# Arduino_MEGA2560_manual.net
KiCad netlist of a schematic drawn in EAGLE
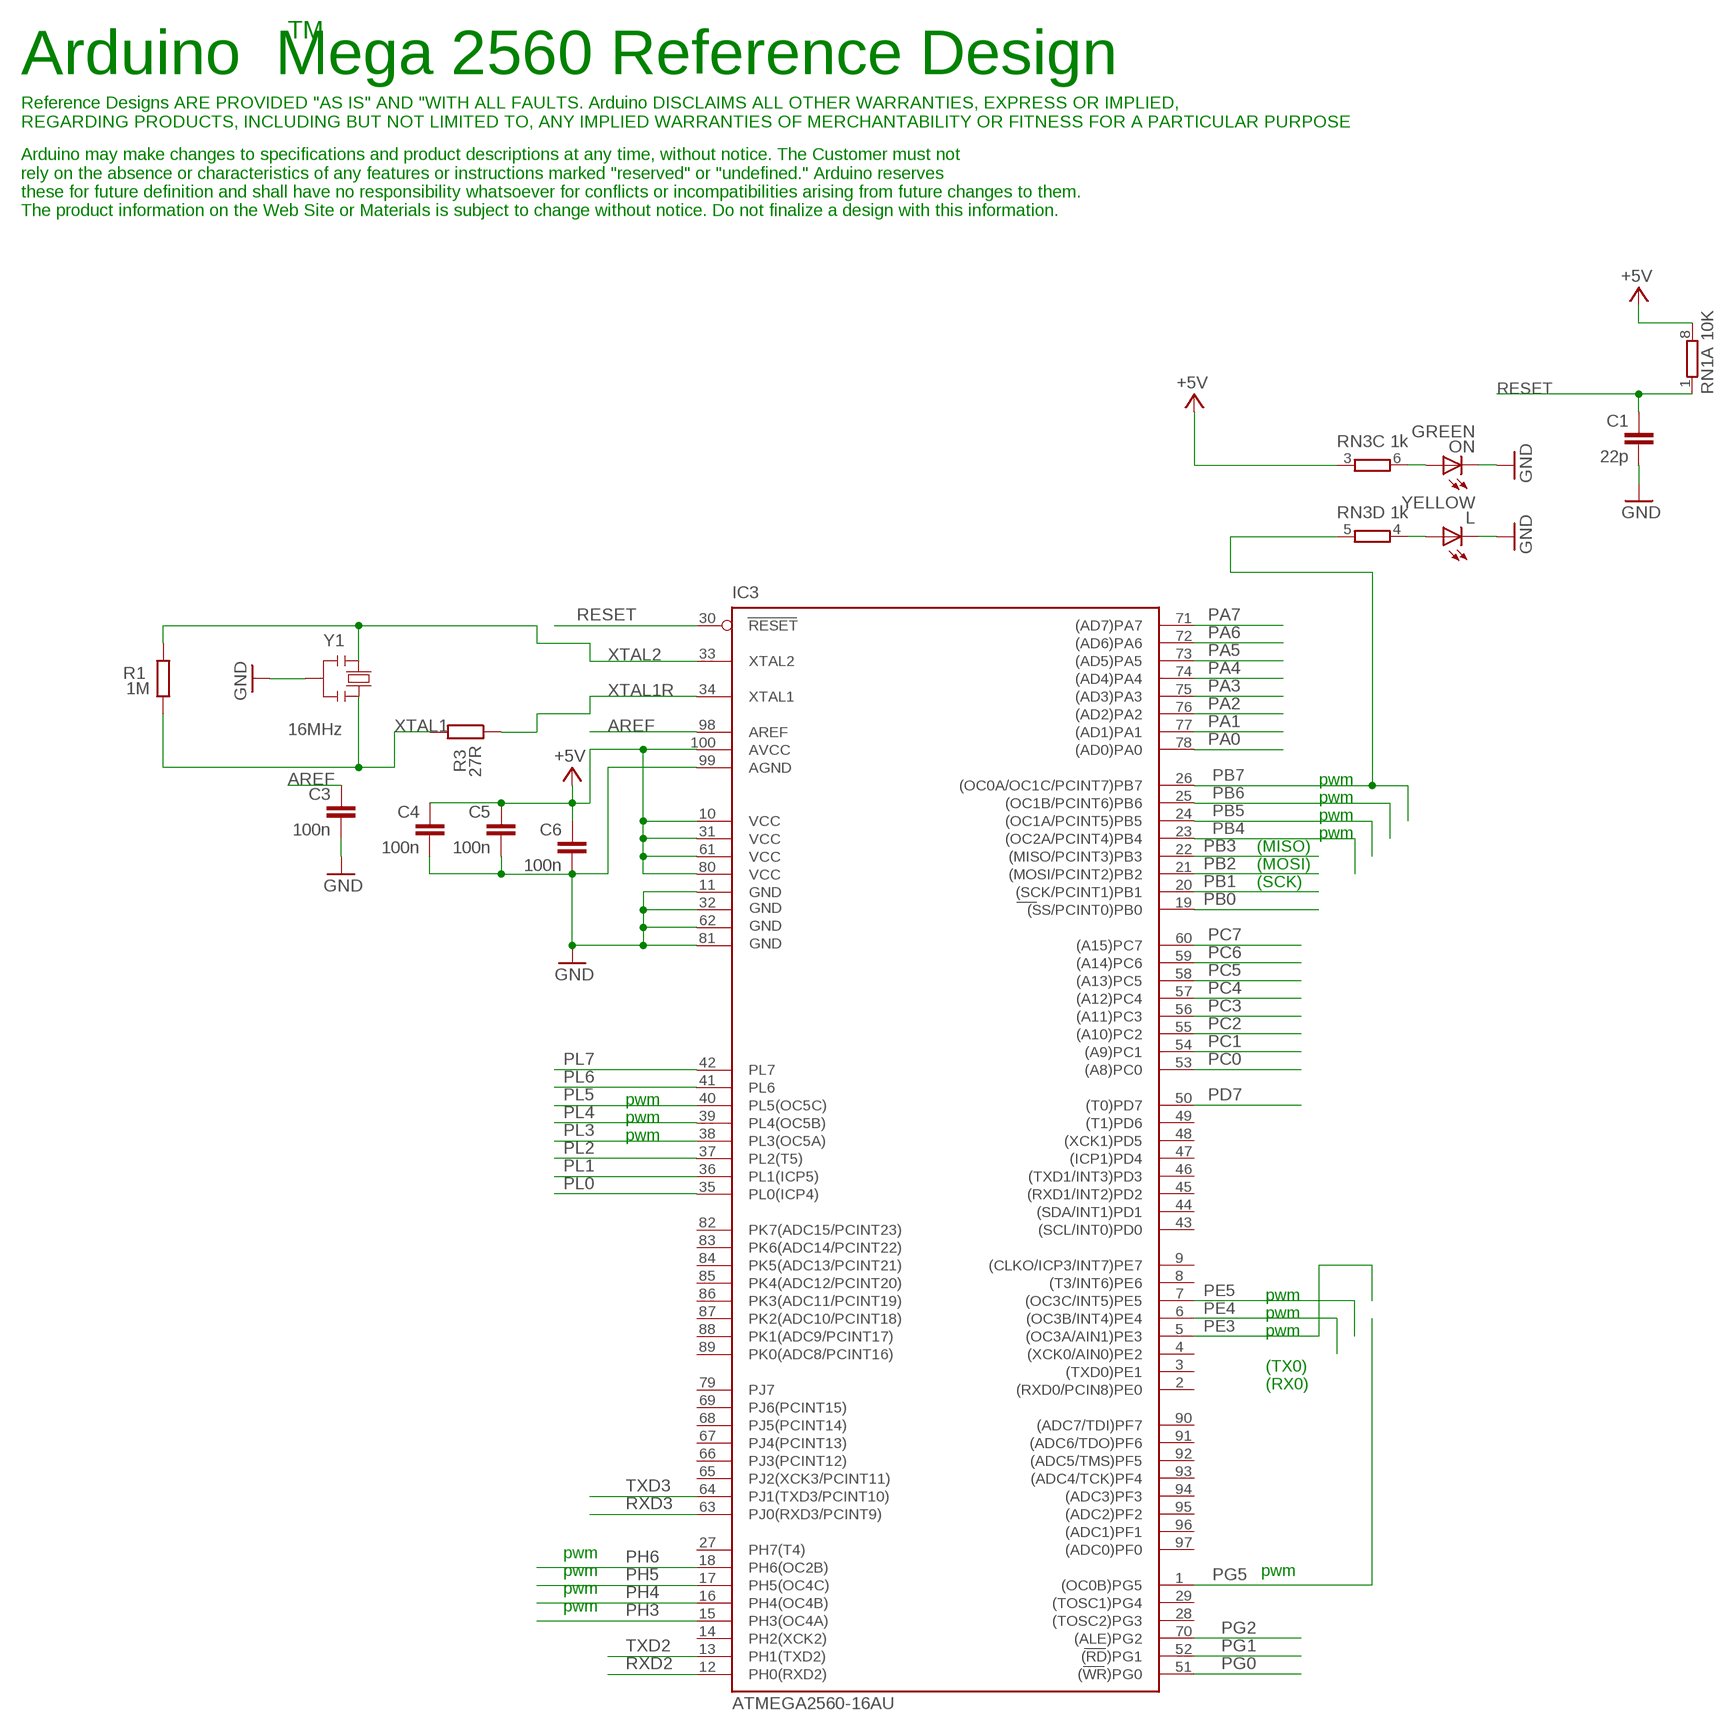
[diagram p0: schematic, sheet 1]

(export (version "E")
  (design (tool "Eeschema 10.0.6"))
  (components
    (comp (ref "C1")
      (value "22p")
      (footprint "eagle-import:C0603-ROUND")
      (libsource (lib "eagle-import") (part "C-EU0603-RND"))
    )
    (comp (ref "C3")
      (value "100n")
      (footprint "eagle-import:C0603-ROUND")
      (libsource (lib "eagle-import") (part "C-EU0603-RND"))
    )
    (comp (ref "C4")
      (value "100n")
      (footprint "eagle-import:C0603-ROUND")
      (libsource (lib "eagle-import") (part "C-EU0603-RND"))
    )
    (comp (ref "C5")
      (value "100n")
      (footprint "eagle-import:C0603-ROUND")
      (libsource (lib "eagle-import") (part "C-EU0603-RND"))
    )
    (comp (ref "C6")
      (value "100n")
      (footprint "eagle-import:C0603-ROUND")
      (libsource (lib "eagle-import") (part "C-EU0603-RND"))
    )
    (comp (ref "IC3")
      (value "ATMEGA2560-16AU")
      (footprint "eagle-import:TQFP100")
      (libsource (lib "eagle-import") (part "ATMEGAAU1280-16"))
    )
    (comp (ref "L")
      (value "YELLOW")
      (footprint "eagle-import:CHIP-LED0805")
      (libsource (lib "eagle-import") (part "LEDCHIP-LED0805"))
    )
    (comp (ref "ON")
      (value "GREEN")
      (footprint "eagle-import:CHIP-LED0805")
      (libsource (lib "eagle-import") (part "LEDCHIP-LED0805"))
    )
    (comp (ref "R1")
      (value "1M")
      (footprint "eagle-import:R0603-ROUND")
      (libsource (lib "eagle-import") (part "R-EU_R0603"))
    )
    (comp (ref "R3")
      (value "27R")
      (footprint "eagle-import:R0603-ROUND")
      (libsource (lib "eagle-import") (part "R-EU_R0603"))
    )
    (comp (ref "RN1")
      (value "10K")
      (footprint "eagle-import:CAT16")
      (libsource (lib "eagle-import") (part "4R-NCAT16"))
    )
    (comp (ref "RN3")
      (value "1k")
      (footprint "eagle-import:CAY16")
      (libsource (lib "eagle-import") (part "4R-NCAY16"))
    )
    (comp (ref "Y1")
      (value "16MHz")
      (footprint "eagle-import:RESONATOR")
      (libsource (lib "eagle-import") (part "RESONATORMU"))
    )
  )
  (nets
    (net (code "1") (name "+5V") (class "Default")
      (node (ref "C4") (pin "1") (pinfunction "1_1") (pintype "passive"))
      (node (ref "C5") (pin "1") (pinfunction "1_1") (pintype "passive"))
      (node (ref "C6") (pin "1") (pinfunction "1_1") (pintype "passive"))
      (node (ref "IC3") (pin "10") (pinfunction "VCC_10") (pintype "power_in"))
      (node (ref "IC3") (pin "100") (pinfunction "AVCC_100") (pintype "power_in"))
      (node (ref "IC3") (pin "31") (pinfunction "VCC1_31") (pintype "power_in"))
      (node (ref "IC3") (pin "61") (pinfunction "VCC2_61") (pintype "power_in"))
      (node (ref "IC3") (pin "80") (pinfunction "VCC3_80") (pintype "power_in"))
      (node (ref "RN1") (pin "8") (pinfunction "2_8") (pintype "passive"))
      (node (ref "RN3") (pin "3") (pinfunction "1_3") (pintype "passive"))
    )
    (net (code "2") (name "/AREF") (class "Default")
      (node (ref "C3") (pin "1") (pinfunction "1_1") (pintype "passive"))
      (node (ref "IC3") (pin "98") (pinfunction "AREF_98") (pintype "bidirectional"))
    )
    (net (code "3") (name "/PA0") (class "Default")
      (node (ref "IC3") (pin "78") (pinfunction "(AD0)PA0_78") (pintype "bidirectional"))
    )
    (net (code "4") (name "/PA1") (class "Default")
      (node (ref "IC3") (pin "77") (pinfunction "(AD1)PA1_77") (pintype "bidirectional"))
    )
    (net (code "5") (name "/PA2") (class "Default")
      (node (ref "IC3") (pin "76") (pinfunction "(AD2)PA2_76") (pintype "bidirectional"))
    )
    (net (code "6") (name "/PA3") (class "Default")
      (node (ref "IC3") (pin "75") (pinfunction "(AD3)PA3_75") (pintype "bidirectional"))
    )
    (net (code "7") (name "/PA4") (class "Default")
      (node (ref "IC3") (pin "74") (pinfunction "(AD4)PA4_74") (pintype "bidirectional"))
    )
    (net (code "8") (name "/PA5") (class "Default")
      (node (ref "IC3") (pin "73") (pinfunction "(AD5)PA5_73") (pintype "bidirectional"))
    )
    (net (code "9") (name "/PA6") (class "Default")
      (node (ref "IC3") (pin "72") (pinfunction "(AD6)PA6_72") (pintype "bidirectional"))
    )
    (net (code "10") (name "/PA7") (class "Default")
      (node (ref "IC3") (pin "71") (pinfunction "(AD7)PA7_71") (pintype "bidirectional"))
    )
    (net (code "11") (name "/PB0") (class "Default")
      (node (ref "IC3") (pin "19") (pinfunction "(SS/PCINT0)PB0_19") (pintype "bidirectional"))
    )
    (net (code "12") (name "/PB1") (class "Default")
      (node (ref "IC3") (pin "20") (pinfunction "(SCK/PCINT1)PB1_20") (pintype "bidirectional"))
    )
    (net (code "13") (name "/PB2") (class "Default")
      (node (ref "IC3") (pin "21") (pinfunction "(MOSI/PCINT2)PB2_21") (pintype "bidirectional"))
    )
    (net (code "14") (name "/PB3") (class "Default")
      (node (ref "IC3") (pin "22") (pinfunction "(MISO/PCINT3)PB3_22") (pintype "bidirectional"))
    )
    (net (code "15") (name "/PB4") (class "Default")
      (node (ref "IC3") (pin "23") (pinfunction "(OC2A/PCINT4)PB4_23") (pintype "bidirectional"))
    )
    (net (code "16") (name "/PB5") (class "Default")
      (node (ref "IC3") (pin "24") (pinfunction "(OC1A/PCINT5)PB5_24") (pintype "bidirectional"))
    )
    (net (code "17") (name "/PB6") (class "Default")
      (node (ref "IC3") (pin "25") (pinfunction "(OC1B/PCINT6)PB6_25") (pintype "bidirectional"))
    )
    (net (code "18") (name "/PB7") (class "Default")
      (node (ref "IC3") (pin "26") (pinfunction "(OC0A/OC1C/PCINT7)PB7_26") (pintype "bidirectional"))
      (node (ref "RN3") (pin "5") (pinfunction "2_5") (pintype "passive"))
    )
    (net (code "19") (name "/PC0") (class "Default")
      (node (ref "IC3") (pin "53") (pinfunction "(A8)PC0_53") (pintype "bidirectional"))
    )
    (net (code "20") (name "/PC1") (class "Default")
      (node (ref "IC3") (pin "54") (pinfunction "(A9)PC1_54") (pintype "bidirectional"))
    )
    (net (code "21") (name "/PC2") (class "Default")
      (node (ref "IC3") (pin "55") (pinfunction "(A10)PC2_55") (pintype "bidirectional"))
    )
    (net (code "22") (name "/PC3") (class "Default")
      (node (ref "IC3") (pin "56") (pinfunction "(A11)PC3_56") (pintype "bidirectional"))
    )
    (net (code "23") (name "/PC4") (class "Default")
      (node (ref "IC3") (pin "57") (pinfunction "(A12)PC4_57") (pintype "bidirectional"))
    )
    (net (code "24") (name "/PC5") (class "Default")
      (node (ref "IC3") (pin "58") (pinfunction "(A13)PC5_58") (pintype "bidirectional"))
    )
    (net (code "25") (name "/PC6") (class "Default")
      (node (ref "IC3") (pin "59") (pinfunction "(A14)PC6_59") (pintype "bidirectional"))
    )
    (net (code "26") (name "/PC7") (class "Default")
      (node (ref "IC3") (pin "60") (pinfunction "(A15)PC7_60") (pintype "bidirectional"))
    )
    (net (code "27") (name "/PD7") (class "Default")
      (node (ref "IC3") (pin "50") (pinfunction "(T0)PD7_50") (pintype "bidirectional"))
    )
    (net (code "28") (name "/PE3") (class "Default")
      (node (ref "IC3") (pin "5") (pinfunction "(OC3A/AIN1)PE3_5") (pintype "bidirectional"))
    )
    (net (code "29") (name "/PE4") (class "Default")
      (node (ref "IC3") (pin "6") (pinfunction "(OC3B/INT4)PE4_6") (pintype "bidirectional"))
    )
    (net (code "30") (name "/PE5") (class "Default")
      (node (ref "IC3") (pin "7") (pinfunction "(OC3C/INT5)PE5_7") (pintype "bidirectional"))
    )
    (net (code "31") (name "/PG0") (class "Default")
      (node (ref "IC3") (pin "51") (pinfunction "(WR)PG0_51") (pintype "bidirectional"))
    )
    (net (code "32") (name "/PG1") (class "Default")
      (node (ref "IC3") (pin "52") (pinfunction "(RD)PG1_52") (pintype "bidirectional"))
    )
    (net (code "33") (name "/PG2") (class "Default")
      (node (ref "IC3") (pin "70") (pinfunction "(ALE)PG2_70") (pintype "bidirectional"))
    )
    (net (code "34") (name "/PG5") (class "Default")
      (node (ref "IC3") (pin "1") (pinfunction "(OC0B)PG5_1") (pintype "bidirectional"))
    )
    (net (code "35") (name "/PH3") (class "Default")
      (node (ref "IC3") (pin "15") (pinfunction "PH3(OC4A)_15") (pintype "bidirectional"))
    )
    (net (code "36") (name "/PH4") (class "Default")
      (node (ref "IC3") (pin "16") (pinfunction "PH4(OC4B)_16") (pintype "bidirectional"))
    )
    (net (code "37") (name "/PH5") (class "Default")
      (node (ref "IC3") (pin "17") (pinfunction "PH5(OC4C)_17") (pintype "bidirectional"))
    )
    (net (code "38") (name "/PH6") (class "Default")
      (node (ref "IC3") (pin "18") (pinfunction "PH6(OC2B)_18") (pintype "bidirectional"))
    )
    (net (code "39") (name "/PL0") (class "Default")
      (node (ref "IC3") (pin "35") (pinfunction "PL0(ICP4)_35") (pintype "bidirectional"))
    )
    (net (code "40") (name "/PL1") (class "Default")
      (node (ref "IC3") (pin "36") (pinfunction "PL1(ICP5)_36") (pintype "bidirectional"))
    )
    (net (code "41") (name "/PL2") (class "Default")
      (node (ref "IC3") (pin "37") (pinfunction "PL2(T5)_37") (pintype "bidirectional"))
    )
    (net (code "42") (name "/PL3") (class "Default")
      (node (ref "IC3") (pin "38") (pinfunction "PL3(OC5A)_38") (pintype "bidirectional"))
    )
    (net (code "43") (name "/PL4") (class "Default")
      (node (ref "IC3") (pin "39") (pinfunction "PL4(OC5B)_39") (pintype "bidirectional"))
    )
    (net (code "44") (name "/PL5") (class "Default")
      (node (ref "IC3") (pin "40") (pinfunction "PL5(OC5C)_40") (pintype "bidirectional"))
    )
    (net (code "45") (name "/PL6") (class "Default")
      (node (ref "IC3") (pin "41") (pinfunction "PL6_41") (pintype "bidirectional"))
    )
    (net (code "46") (name "/PL7") (class "Default")
      (node (ref "IC3") (pin "42") (pinfunction "PL7_42") (pintype "bidirectional"))
    )
    (net (code "47") (name "/RESET") (class "Default")
      (node (ref "C1") (pin "1") (pinfunction "1_1") (pintype "passive"))
      (node (ref "IC3") (pin "30") (pinfunction "RESET_30") (pintype "input"))
      (node (ref "RN1") (pin "1") (pinfunction "1_1") (pintype "passive"))
    )
    (net (code "48") (name "/RXD2") (class "Default")
      (node (ref "IC3") (pin "12") (pinfunction "PH0(RXD2)_12") (pintype "bidirectional"))
    )
    (net (code "49") (name "/RXD3") (class "Default")
      (node (ref "IC3") (pin "63") (pinfunction "PJ0(RXD3/PCINT9)_63") (pintype "bidirectional"))
    )
    (net (code "50") (name "/TXD2") (class "Default")
      (node (ref "IC3") (pin "13") (pinfunction "PH1(TXD2)_13") (pintype "bidirectional"))
    )
    (net (code "51") (name "/TXD3") (class "Default")
      (node (ref "IC3") (pin "64") (pinfunction "PJ1(TXD3/PCINT10)_64") (pintype "bidirectional"))
    )
    (net (code "52") (name "/XTAL1") (class "Default")
      (node (ref "R1") (pin "1") (pinfunction "1_1") (pintype "passive"))
      (node (ref "R3") (pin "2") (pinfunction "2_2") (pintype "passive"))
      (node (ref "Y1") (pin "3") (pinfunction "3_3") (pintype "passive"))
    )
    (net (code "53") (name "/XTAL1R") (class "Default")
      (node (ref "IC3") (pin "34") (pinfunction "XTAL1_34") (pintype "input"))
      (node (ref "R3") (pin "1") (pinfunction "1_1") (pintype "passive"))
    )
    (net (code "54") (name "/XTAL2") (class "Default")
      (node (ref "IC3") (pin "33") (pinfunction "XTAL2_33") (pintype "output"))
      (node (ref "R1") (pin "2") (pinfunction "2_2") (pintype "passive"))
      (node (ref "Y1") (pin "1") (pinfunction "1_1") (pintype "passive"))
    )
    (net (code "55") (name "GND") (class "Default")
      (node (ref "C1") (pin "2") (pinfunction "2_2") (pintype "passive"))
      (node (ref "C3") (pin "2") (pinfunction "2_2") (pintype "passive"))
      (node (ref "C4") (pin "2") (pinfunction "2_2") (pintype "passive"))
      (node (ref "C5") (pin "2") (pinfunction "2_2") (pintype "passive"))
      (node (ref "C6") (pin "2") (pinfunction "2_2") (pintype "passive"))
      (node (ref "IC3") (pin "11") (pinfunction "GND_11") (pintype "power_in"))
      (node (ref "IC3") (pin "32") (pinfunction "GND1_32") (pintype "power_in"))
      (node (ref "IC3") (pin "62") (pinfunction "GND2_62") (pintype "power_in"))
      (node (ref "IC3") (pin "81") (pinfunction "GND3_81") (pintype "power_in"))
      (node (ref "IC3") (pin "99") (pinfunction "AGND_99") (pintype "power_in"))
      (node (ref "L") (pin "C") (pinfunction "C_C") (pintype "passive"))
      (node (ref "ON") (pin "C") (pinfunction "C_C") (pintype "passive"))
      (node (ref "Y1") (pin "2") (pinfunction "2_2") (pintype "passive"))
    )
    (net (code "56") (name "Net-(RN3C-2)") (class "Default")
      (node (ref "ON") (pin "A") (pinfunction "A_A") (pintype "passive"))
      (node (ref "RN3") (pin "6") (pinfunction "2_6") (pintype "passive"))
    )
    (net (code "57") (name "Net-(RN3D-1)") (class "Default")
      (node (ref "L") (pin "A") (pinfunction "A_A") (pintype "passive"))
      (node (ref "RN3") (pin "4") (pinfunction "1_4") (pintype "passive"))
    )
    (net (code "58") (name "unconnected-(IC3-(ADC0)PF0-Pad97)") (class "Default")
      (node (ref "IC3") (pin "97") (pinfunction "(ADC0)PF0_97") (pintype "bidirectional"))
    )
    (net (code "59") (name "unconnected-(IC3-(ADC1)PF1-Pad96)") (class "Default")
      (node (ref "IC3") (pin "96") (pinfunction "(ADC1)PF1_96") (pintype "bidirectional"))
    )
    (net (code "60") (name "unconnected-(IC3-(ADC2)PF2-Pad95)") (class "Default")
      (node (ref "IC3") (pin "95") (pinfunction "(ADC2)PF2_95") (pintype "bidirectional"))
    )
    (net (code "61") (name "unconnected-(IC3-(ADC3)PF3-Pad94)") (class "Default")
      (node (ref "IC3") (pin "94") (pinfunction "(ADC3)PF3_94") (pintype "bidirectional"))
    )
    (net (code "62") (name "unconnected-(IC3-(ADC4{slash}TCK)PF4-Pad93)") (class "Default")
      (node (ref "IC3") (pin "93") (pinfunction "(ADC4/TCK)PF4_93") (pintype "bidirectional"))
    )
    (net (code "63") (name "unconnected-(IC3-(ADC5{slash}TMS)PF5-Pad92)") (class "Default")
      (node (ref "IC3") (pin "92") (pinfunction "(ADC5/TMS)PF5_92") (pintype "bidirectional"))
    )
    (net (code "64") (name "unconnected-(IC3-(ADC6{slash}TDO)PF6-Pad91)") (class "Default")
      (node (ref "IC3") (pin "91") (pinfunction "(ADC6/TDO)PF6_91") (pintype "bidirectional"))
    )
    (net (code "65") (name "unconnected-(IC3-(ADC7{slash}TDI)PF7-Pad90)") (class "Default")
      (node (ref "IC3") (pin "90") (pinfunction "(ADC7/TDI)PF7_90") (pintype "bidirectional"))
    )
    (net (code "66") (name "unconnected-(IC3-(CLKO{slash}ICP3{slash}INT7)PE7-Pad9)") (class "Default")
      (node (ref "IC3") (pin "9") (pinfunction "(CLKO/ICP3/INT7)PE7_9") (pintype "bidirectional"))
    )
    (net (code "67") (name "unconnected-(IC3-(ICP1)PD4-Pad47)") (class "Default")
      (node (ref "IC3") (pin "47") (pinfunction "(ICP1)PD4_47") (pintype "bidirectional"))
    )
    (net (code "68") (name "unconnected-(IC3-(RXD0{slash}PCIN8)PE0-Pad2)") (class "Default")
      (node (ref "IC3") (pin "2") (pinfunction "(RXD0/PCIN8)PE0_2") (pintype "bidirectional"))
    )
    (net (code "69") (name "unconnected-(IC3-(RXD1{slash}INT2)PD2-Pad45)") (class "Default")
      (node (ref "IC3") (pin "45") (pinfunction "(RXD1/INT2)PD2_45") (pintype "bidirectional"))
    )
    (net (code "70") (name "unconnected-(IC3-(SCL{slash}INT0)PD0-Pad43)") (class "Default")
      (node (ref "IC3") (pin "43") (pinfunction "(SCL/INT0)PD0_43") (pintype "bidirectional"))
    )
    (net (code "71") (name "unconnected-(IC3-(SDA{slash}INT1)PD1-Pad44)") (class "Default")
      (node (ref "IC3") (pin "44") (pinfunction "(SDA/INT1)PD1_44") (pintype "bidirectional"))
    )
    (net (code "72") (name "unconnected-(IC3-(T1)PD6-Pad49)") (class "Default")
      (node (ref "IC3") (pin "49") (pinfunction "(T1)PD6_49") (pintype "bidirectional"))
    )
    (net (code "73") (name "unconnected-(IC3-(T3{slash}INT6)PE6-Pad8)") (class "Default")
      (node (ref "IC3") (pin "8") (pinfunction "(T3/INT6)PE6_8") (pintype "bidirectional"))
    )
    (net (code "74") (name "unconnected-(IC3-(TOSC1)PG4-Pad29)") (class "Default")
      (node (ref "IC3") (pin "29") (pinfunction "(TOSC1)PG4_29") (pintype "bidirectional"))
    )
    (net (code "75") (name "unconnected-(IC3-(TOSC2)PG3-Pad28)") (class "Default")
      (node (ref "IC3") (pin "28") (pinfunction "(TOSC2)PG3_28") (pintype "bidirectional"))
    )
    (net (code "76") (name "unconnected-(IC3-(TXD0)PE1-Pad3)") (class "Default")
      (node (ref "IC3") (pin "3") (pinfunction "(TXD0)PE1_3") (pintype "bidirectional"))
    )
    (net (code "77") (name "unconnected-(IC3-(TXD1{slash}INT3)PD3-Pad46)") (class "Default")
      (node (ref "IC3") (pin "46") (pinfunction "(TXD1/INT3)PD3_46") (pintype "bidirectional"))
    )
    (net (code "78") (name "unconnected-(IC3-(XCK0{slash}AIN0)PE2-Pad4)") (class "Default")
      (node (ref "IC3") (pin "4") (pinfunction "(XCK0/AIN0)PE2_4") (pintype "bidirectional"))
    )
    (net (code "79") (name "unconnected-(IC3-(XCK1)PD5-Pad48)") (class "Default")
      (node (ref "IC3") (pin "48") (pinfunction "(XCK1)PD5_48") (pintype "bidirectional"))
    )
    (net (code "80") (name "unconnected-(IC3-PH2(XCK2)-Pad14)") (class "Default")
      (node (ref "IC3") (pin "14") (pinfunction "PH2(XCK2)_14") (pintype "bidirectional"))
    )
    (net (code "81") (name "unconnected-(IC3-PH7(T4)-Pad27)") (class "Default")
      (node (ref "IC3") (pin "27") (pinfunction "PH7(T4)_27") (pintype "bidirectional"))
    )
    (net (code "82") (name "unconnected-(IC3-PJ2(XCK3{slash}PCINT11)-Pad65)") (class "Default")
      (node (ref "IC3") (pin "65") (pinfunction "PJ2(XCK3/PCINT11)_65") (pintype "bidirectional"))
    )
    (net (code "83") (name "unconnected-(IC3-PJ3(PCINT12)-Pad66)") (class "Default")
      (node (ref "IC3") (pin "66") (pinfunction "PJ3(PCINT12)_66") (pintype "bidirectional"))
    )
    (net (code "84") (name "unconnected-(IC3-PJ4(PCINT13)-Pad67)") (class "Default")
      (node (ref "IC3") (pin "67") (pinfunction "PJ4(PCINT13)_67") (pintype "bidirectional"))
    )
    (net (code "85") (name "unconnected-(IC3-PJ5(PCINT14)-Pad68)") (class "Default")
      (node (ref "IC3") (pin "68") (pinfunction "PJ5(PCINT14)_68") (pintype "bidirectional"))
    )
    (net (code "86") (name "unconnected-(IC3-PJ6(PCINT15)-Pad69)") (class "Default")
      (node (ref "IC3") (pin "69") (pinfunction "PJ6(PCINT15)_69") (pintype "bidirectional"))
    )
    (net (code "87") (name "unconnected-(IC3-PJ7-Pad79)") (class "Default")
      (node (ref "IC3") (pin "79") (pinfunction "PJ7_79") (pintype "bidirectional"))
    )
    (net (code "88") (name "unconnected-(IC3-PK0(ADC8{slash}PCINT16)-Pad89)") (class "Default")
      (node (ref "IC3") (pin "89") (pinfunction "PK0(ADC8/PCINT16)_89") (pintype "bidirectional"))
    )
    (net (code "89") (name "unconnected-(IC3-PK1(ADC9{slash}PCINT17)-Pad88)") (class "Default")
      (node (ref "IC3") (pin "88") (pinfunction "PK1(ADC9/PCINT17)_88") (pintype "bidirectional"))
    )
    (net (code "90") (name "unconnected-(IC3-PK2(ADC10{slash}PCINT18)-Pad87)") (class "Default")
      (node (ref "IC3") (pin "87") (pinfunction "PK2(ADC10/PCINT18)_87") (pintype "bidirectional"))
    )
    (net (code "91") (name "unconnected-(IC3-PK3(ADC11{slash}PCINT19)-Pad86)") (class "Default")
      (node (ref "IC3") (pin "86") (pinfunction "PK3(ADC11/PCINT19)_86") (pintype "bidirectional"))
    )
    (net (code "92") (name "unconnected-(IC3-PK4(ADC12{slash}PCINT20)-Pad85)") (class "Default")
      (node (ref "IC3") (pin "85") (pinfunction "PK4(ADC12/PCINT20)_85") (pintype "bidirectional"))
    )
    (net (code "93") (name "unconnected-(IC3-PK5(ADC13{slash}PCINT21)-Pad84)") (class "Default")
      (node (ref "IC3") (pin "84") (pinfunction "PK5(ADC13/PCINT21)_84") (pintype "bidirectional"))
    )
    (net (code "94") (name "unconnected-(IC3-PK6(ADC14{slash}PCINT22)-Pad83)") (class "Default")
      (node (ref "IC3") (pin "83") (pinfunction "PK6(ADC14/PCINT22)_83") (pintype "bidirectional"))
    )
    (net (code "95") (name "unconnected-(IC3-PK7(ADC15{slash}PCINT23)-Pad82)") (class "Default")
      (node (ref "IC3") (pin "82") (pinfunction "PK7(ADC15/PCINT23)_82") (pintype "bidirectional"))
    )
  )
)
